# memory.net
KiCad netlist of a schematic drawn in EAGLE
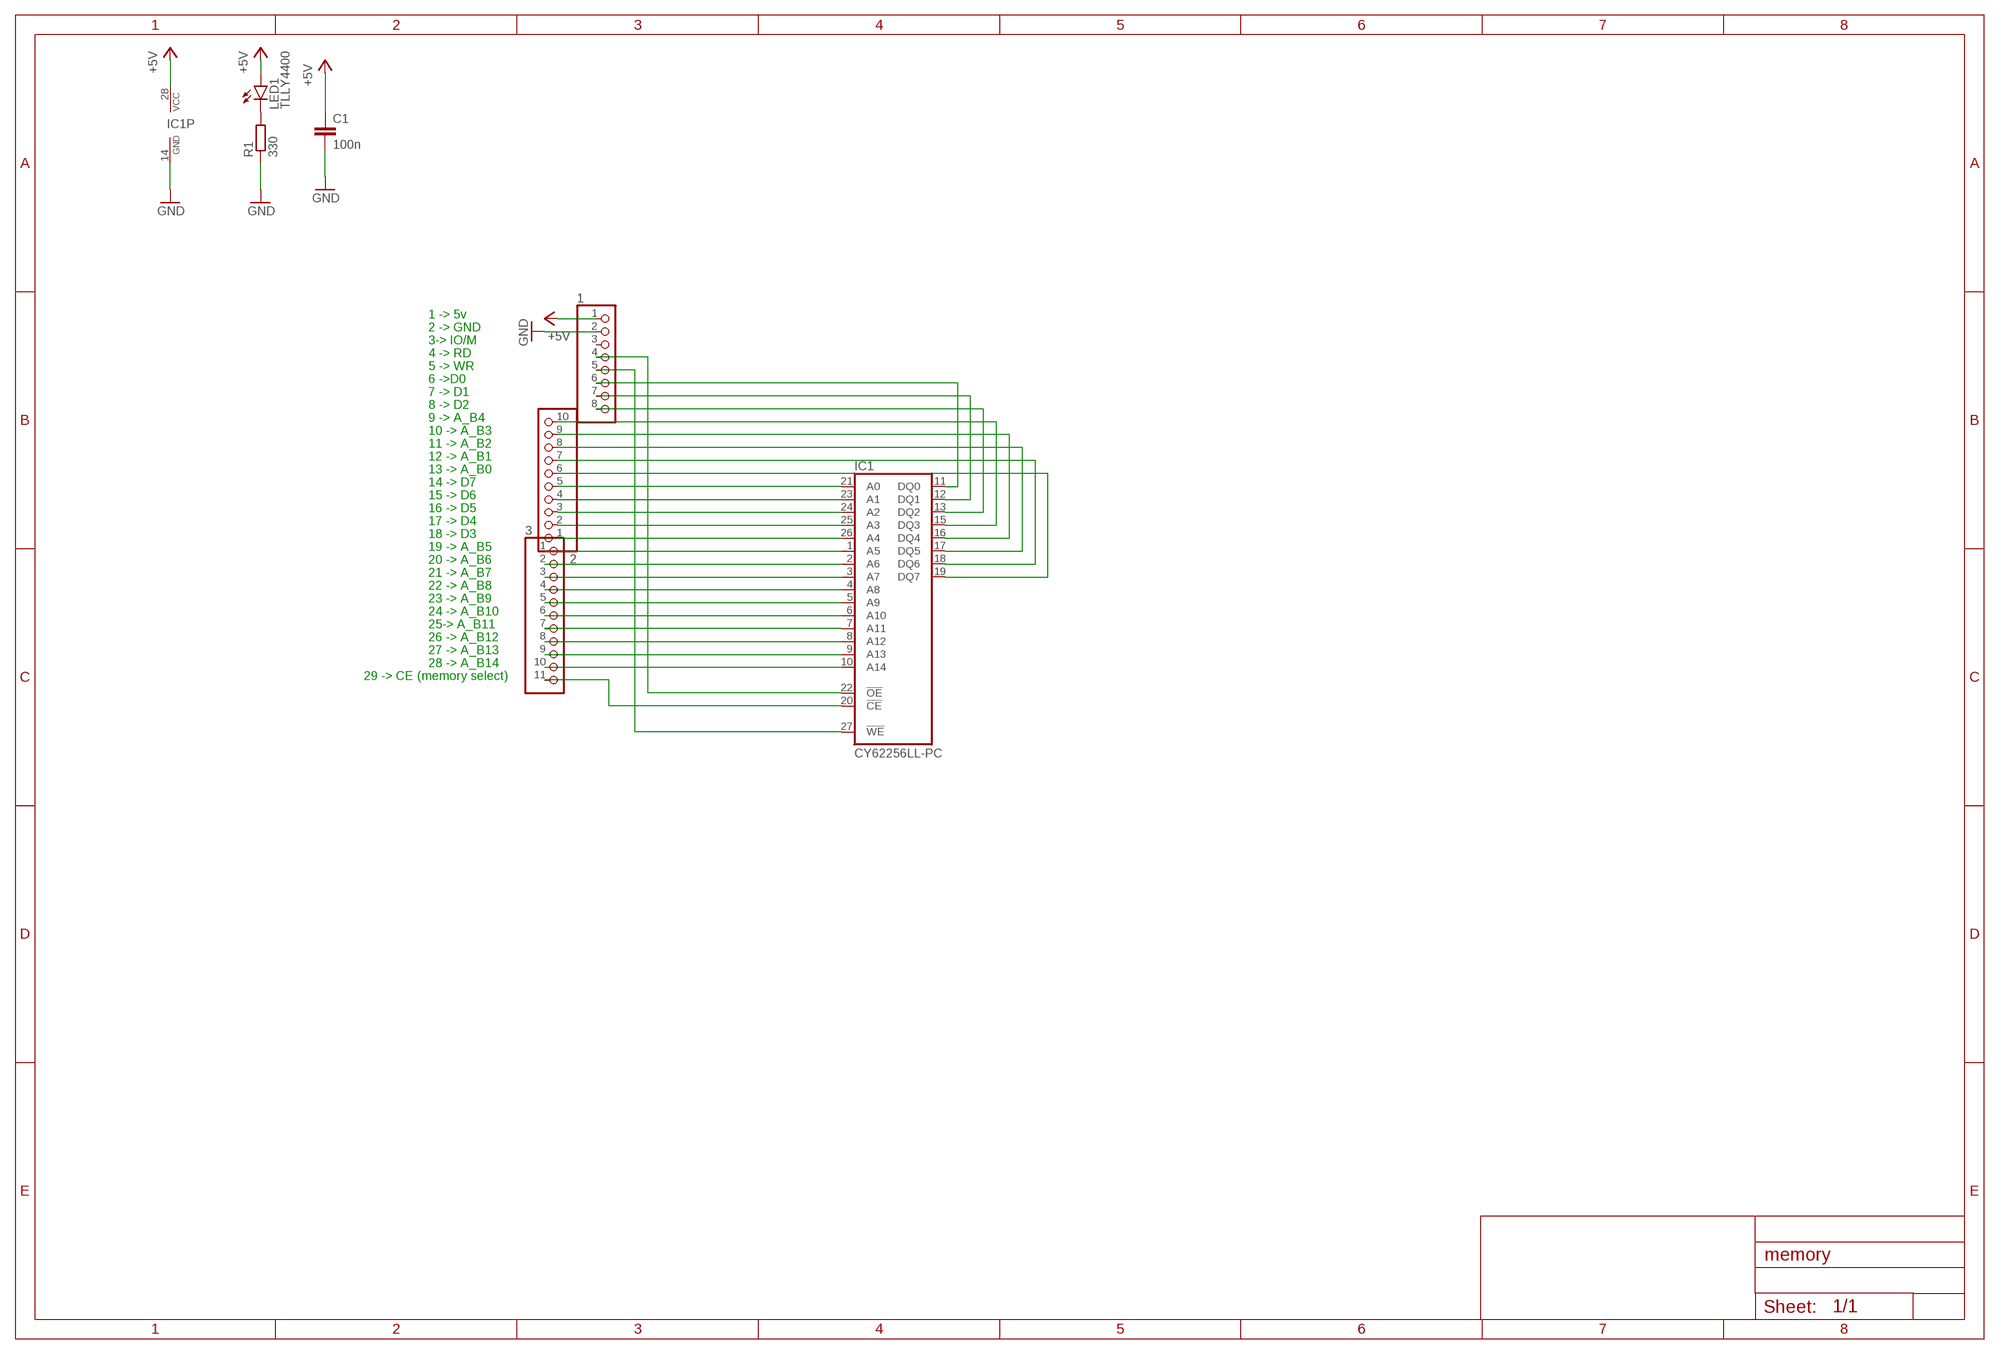
[diagram p0: schematic, sheet 1]

(export (version "E")
  (design (tool "Eeschema 10.0.6"))
  (components
    (comp (ref "1")
      (value "PINHD-1X8/90")
      (footprint "eagle-import:1X08_90")
      (libsource (lib "eagle-import") (part "PINHD-1X8/90"))
    )
    (comp (ref "2")
      (value "PINHD-1X10/90")
      (footprint "eagle-import:1X10_90")
      (libsource (lib "eagle-import") (part "PINHD-1X10/90"))
    )
    (comp (ref "3")
      (value "PINHD-1X11/90")
      (footprint "eagle-import:1X11_90")
      (libsource (lib "eagle-import") (part "PINHD-1X11/90"))
    )
    (comp (ref "C1")
      (value "100n")
      (footprint "eagle-import:C025-025X050")
      (libsource (lib "eagle-import") (part "C-EU025-025X050"))
    )
    (comp (ref "IC1")
      (value "CY62256LL-PC")
      (footprint "eagle-import:DIL28-6")
      (libsource (lib "eagle-import") (part "CY62256LL-?PC"))
    )
    (comp (ref "LED1")
      (value "TLLY4400")
      (footprint "eagle-import:LED3MM")
      (fields (field (name "MF") "VISHAY SEMICONDUCTOR"))
      (libsource (lib "eagle-import") (part "TLLY4400"))
    )
    (comp (ref "R1")
      (value "330")
      (footprint "eagle-import:0207_7")
      (libsource (lib "eagle-import") (part "R-EU_0207/7"))
    )
  )
  (nets
    (net (code "1") (name "+5V") (class "Default")
      (node (ref "1") (pin "1") (pinfunction "1_1") (pintype "passive"))
      (node (ref "C1") (pin "1") (pinfunction "1_1") (pintype "passive"))
      (node (ref "IC1") (pin "28") (pinfunction "VCC_28") (pintype "power_in"))
      (node (ref "LED1") (pin "A") (pinfunction "A_A") (pintype "passive"))
    )
    (net (code "2") (name "GND") (class "Default")
      (node (ref "1") (pin "2") (pinfunction "2_2") (pintype "passive"))
      (node (ref "C1") (pin "2") (pinfunction "2_2") (pintype "passive"))
      (node (ref "IC1") (pin "14") (pinfunction "GND_14") (pintype "power_in"))
      (node (ref "R1") (pin "1") (pinfunction "1_1") (pintype "passive"))
    )
    (net (code "3") (name "Net-(IC1A-A0)") (class "Default")
      (node (ref "2") (pin "5") (pinfunction "5_5") (pintype "passive"))
      (node (ref "IC1") (pin "21") (pinfunction "A0_21") (pintype "input"))
    )
    (net (code "4") (name "Net-(IC1A-A1)") (class "Default")
      (node (ref "2") (pin "4") (pinfunction "4_4") (pintype "passive"))
      (node (ref "IC1") (pin "23") (pinfunction "A1_23") (pintype "input"))
    )
    (net (code "5") (name "Net-(IC1A-A2)") (class "Default")
      (node (ref "2") (pin "3") (pinfunction "3_3") (pintype "passive"))
      (node (ref "IC1") (pin "24") (pinfunction "A2_24") (pintype "input"))
    )
    (net (code "6") (name "Net-(IC1A-A3)") (class "Default")
      (node (ref "2") (pin "2") (pinfunction "2_2") (pintype "passive"))
      (node (ref "IC1") (pin "25") (pinfunction "A3_25") (pintype "input"))
    )
    (net (code "7") (name "Net-(IC1A-A4)") (class "Default")
      (node (ref "2") (pin "1") (pinfunction "1_1") (pintype "passive"))
      (node (ref "IC1") (pin "26") (pinfunction "A4_26") (pintype "input"))
    )
    (net (code "8") (name "Net-(IC1A-A5)") (class "Default")
      (node (ref "3") (pin "1") (pinfunction "1_1") (pintype "passive"))
      (node (ref "IC1") (pin "1") (pinfunction "A5_1") (pintype "input"))
    )
    (net (code "9") (name "Net-(IC1A-A6)") (class "Default")
      (node (ref "3") (pin "2") (pinfunction "2_2") (pintype "passive"))
      (node (ref "IC1") (pin "2") (pinfunction "A6_2") (pintype "input"))
    )
    (net (code "10") (name "Net-(IC1A-A7)") (class "Default")
      (node (ref "3") (pin "3") (pinfunction "3_3") (pintype "passive"))
      (node (ref "IC1") (pin "3") (pinfunction "A7_3") (pintype "input"))
    )
    (net (code "11") (name "Net-(IC1A-A8)") (class "Default")
      (node (ref "3") (pin "4") (pinfunction "4_4") (pintype "passive"))
      (node (ref "IC1") (pin "4") (pinfunction "A8_4") (pintype "input"))
    )
    (net (code "12") (name "Net-(IC1A-A9)") (class "Default")
      (node (ref "3") (pin "5") (pinfunction "5_5") (pintype "passive"))
      (node (ref "IC1") (pin "5") (pinfunction "A9_5") (pintype "input"))
    )
    (net (code "13") (name "Net-(IC1A-A10)") (class "Default")
      (node (ref "3") (pin "6") (pinfunction "6_6") (pintype "passive"))
      (node (ref "IC1") (pin "6") (pinfunction "A10_6") (pintype "input"))
    )
    (net (code "14") (name "Net-(IC1A-A11)") (class "Default")
      (node (ref "3") (pin "7") (pinfunction "7_7") (pintype "passive"))
      (node (ref "IC1") (pin "7") (pinfunction "A11_7") (pintype "input"))
    )
    (net (code "15") (name "Net-(IC1A-A12)") (class "Default")
      (node (ref "3") (pin "8") (pinfunction "8_8") (pintype "passive"))
      (node (ref "IC1") (pin "8") (pinfunction "A12_8") (pintype "input"))
    )
    (net (code "16") (name "Net-(IC1A-A13)") (class "Default")
      (node (ref "3") (pin "9") (pinfunction "9_9") (pintype "passive"))
      (node (ref "IC1") (pin "9") (pinfunction "A13_9") (pintype "input"))
    )
    (net (code "17") (name "Net-(IC1A-A14)") (class "Default")
      (node (ref "3") (pin "10") (pinfunction "10_10") (pintype "passive"))
      (node (ref "IC1") (pin "10") (pinfunction "A14_10") (pintype "input"))
    )
    (net (code "18") (name "Net-(IC1A-DQ0)") (class "Default")
      (node (ref "1") (pin "6") (pinfunction "6_6") (pintype "passive"))
      (node (ref "IC1") (pin "11") (pinfunction "DQ0_11") (pintype "bidirectional"))
    )
    (net (code "19") (name "Net-(IC1A-DQ1)") (class "Default")
      (node (ref "1") (pin "7") (pinfunction "7_7") (pintype "passive"))
      (node (ref "IC1") (pin "12") (pinfunction "DQ1_12") (pintype "bidirectional"))
    )
    (net (code "20") (name "Net-(IC1A-DQ2)") (class "Default")
      (node (ref "1") (pin "8") (pinfunction "8_8") (pintype "passive"))
      (node (ref "IC1") (pin "13") (pinfunction "DQ2_13") (pintype "bidirectional"))
    )
    (net (code "21") (name "Net-(IC1A-DQ3)") (class "Default")
      (node (ref "2") (pin "10") (pinfunction "10_10") (pintype "passive"))
      (node (ref "IC1") (pin "15") (pinfunction "DQ3_15") (pintype "bidirectional"))
    )
    (net (code "22") (name "Net-(IC1A-DQ4)") (class "Default")
      (node (ref "2") (pin "9") (pinfunction "9_9") (pintype "passive"))
      (node (ref "IC1") (pin "16") (pinfunction "DQ4_16") (pintype "bidirectional"))
    )
    (net (code "23") (name "Net-(IC1A-DQ5)") (class "Default")
      (node (ref "2") (pin "8") (pinfunction "8_8") (pintype "passive"))
      (node (ref "IC1") (pin "17") (pinfunction "DQ5_17") (pintype "bidirectional"))
    )
    (net (code "24") (name "Net-(IC1A-DQ6)") (class "Default")
      (node (ref "2") (pin "7") (pinfunction "7_7") (pintype "passive"))
      (node (ref "IC1") (pin "18") (pinfunction "DQ6_18") (pintype "bidirectional"))
    )
    (net (code "25") (name "Net-(IC1A-DQ7)") (class "Default")
      (node (ref "2") (pin "6") (pinfunction "6_6") (pintype "passive"))
      (node (ref "IC1") (pin "19") (pinfunction "DQ7_19") (pintype "bidirectional"))
    )
    (net (code "26") (name "Net-(IC1A-~{CE})") (class "Default")
      (node (ref "3") (pin "11") (pinfunction "11_11") (pintype "passive"))
      (node (ref "IC1") (pin "20") (pinfunction "~{CE}_20") (pintype "input"))
    )
    (net (code "27") (name "Net-(IC1A-~{OE})") (class "Default")
      (node (ref "1") (pin "4") (pinfunction "4_4") (pintype "passive"))
      (node (ref "IC1") (pin "22") (pinfunction "~{OE}_22") (pintype "input"))
    )
    (net (code "28") (name "Net-(IC1A-~{WE})") (class "Default")
      (node (ref "1") (pin "5") (pinfunction "5_5") (pintype "passive"))
      (node (ref "IC1") (pin "27") (pinfunction "~{WE}_27") (pintype "input"))
    )
    (net (code "29") (name "Net-(LED1-C)") (class "Default")
      (node (ref "LED1") (pin "K") (pinfunction "C_K") (pintype "passive"))
      (node (ref "R1") (pin "2") (pinfunction "2_2") (pintype "passive"))
    )
    (net (code "30") (name "unconnected-(1-Pad3)") (class "Default")
      (node (ref "1") (pin "3") (pinfunction "3_3") (pintype "passive"))
    )
  )
)
